# LoRa_XCVR.net
KiCad netlist of a schematic drawn in Altium Designer
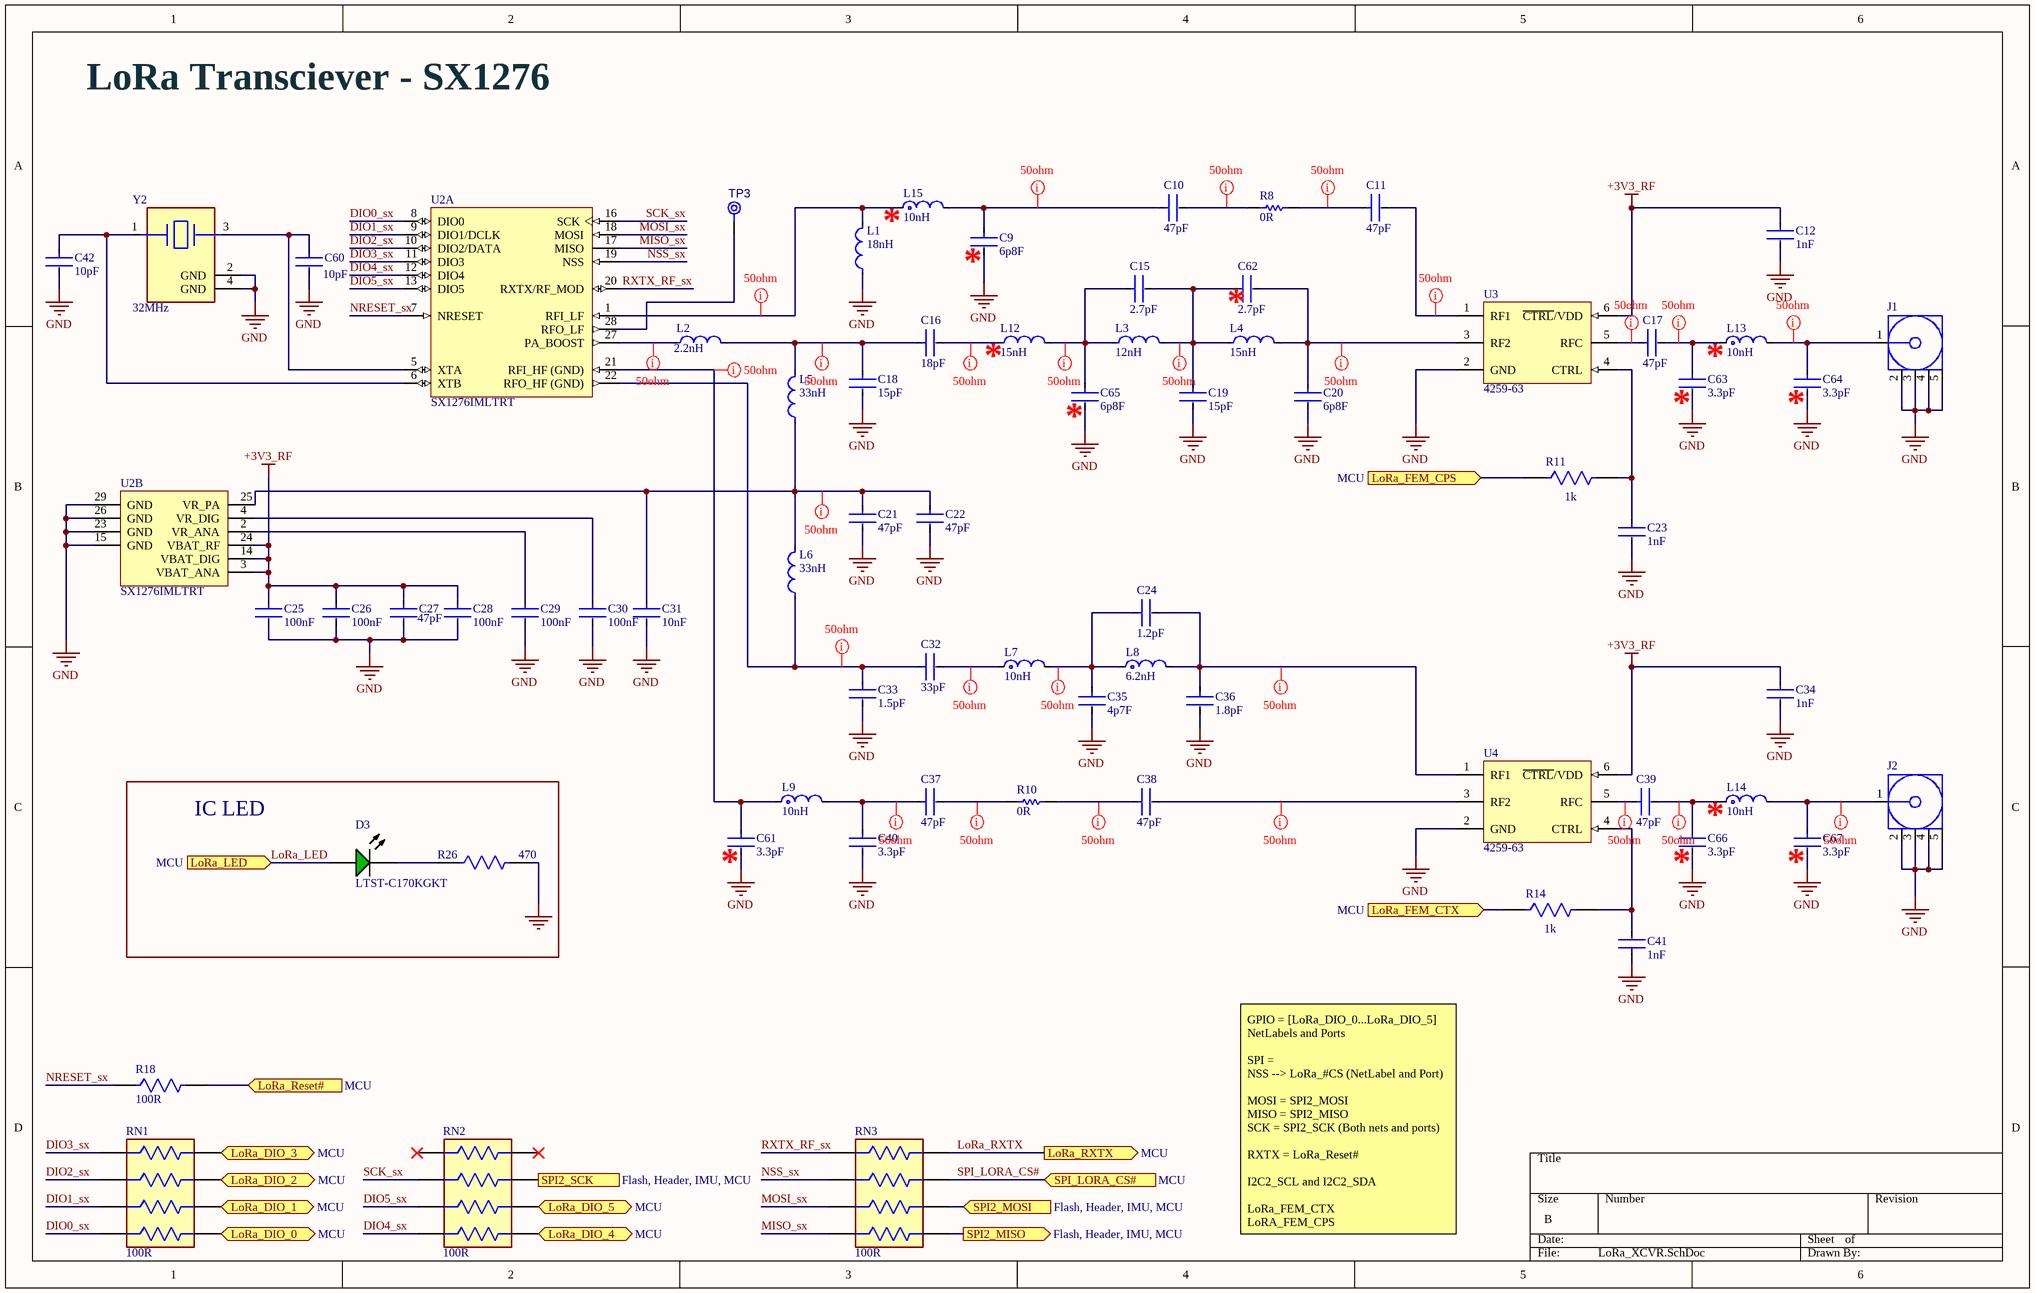
[diagram p0: LoRa_XCVR.SchDoc]

(export (version "E")
  (design (tool "Eeschema 10.0.6"))
  (components
    (comp (ref "C9")
      (value "6p8F")
      (footprint "FP-GJM155-0_05-IPC_A")
      (description "Multi-Layer Ceramic Capacitor 6.8pF C0G  ±0.1pF 0402 Paper T/R")
      (libsource (lib "Altium Content Vault") (part "02cd4be3c70576c341d710602a673aa"))
    )
    (comp (ref "C10")
      (value "47pF")
      (footprint "FP-GJM155-0_05-MFG")
      (description "Multi-Layer Ceramic Capacitor 47pF C0G  ±5% 0402 Paper T/R")
      (fields (field (name "TOLERANCE") "5%"))
      (libsource (lib "Altium Content Vault") (part "02cd4be3c70576c341d710602a673aa"))
    )
    (comp (ref "C11")
      (value "47pF")
      (footprint "FP-GJM155-0_05-MFG")
      (description "Multi-Layer Ceramic Capacitor 47pF C0G  ±5% 0402 Paper T/R")
      (fields (field (name "TOLERANCE") "5%"))
      (libsource (lib "Altium Content Vault") (part "02cd4be3c70576c341d710602a673aa"))
    )
    (comp (ref "C12")
      (value "1nF")
      (footprint "FP-GRM155-0_05-IPC_C")
      (description "Chip Multilayer Ceramic Capacitors for General Purpose, 0402, 1000pF, X7R, 15%, 10%, 100V")
      (fields (field (name "TOLERANCE") "10%") (field (name "VOLTAGE") "100V"))
      (libsource (lib "Altium Content Vault") (part "02cd4be3c70576c341d710602a673aa"))
    )
    (comp (ref "C15")
      (value "2.7pF")
      (footprint "FP-GJM155-0_05-IPC_A")
      (description "Multi-Layer Ceramic Capacitor 2.7pF C0G  ±0.1pF 0402 Paper T/R")
      (fields (field (name "VOLTAGE") "50V"))
      (libsource (lib "Altium Content Vault") (part "02cd4be3c70576c341d710602a673aa"))
    )
    (comp (ref "C16")
      (value "18pF")
      (footprint "FP-GJM155-0_05-IPC_B")
      (description "Multi-Layer Ceramic Capacitor 18pF C0G  ±5% 0402 Paper T/R")
      (fields (field (name "VOLTAGE") "50V") (field (name "TOLERANCE") "5%"))
      (libsource (lib "Altium Content Vault") (part "02cd4be3c70576c341d710602a673aa"))
    )
    (comp (ref "C17")
      (value "47pF")
      (footprint "FP-GJM155-0_05-MFG")
      (description "Multi-Layer Ceramic Capacitor 47pF C0G  ±5% 0402 Paper T/R")
      (fields (field (name "TOLERANCE") "5%"))
      (libsource (lib "Altium Content Vault") (part "02cd4be3c70576c341d710602a673aa"))
    )
    (comp (ref "C18")
      (value "15pF")
      (footprint "FP-GJM155-0_05-IPC_A")
      (description "Multi-Layer Ceramic Capacitor 15pF C0G  ±5% 0402 Paper T/R")
      (fields (field (name "TOLERANCE") "5%") (field (name "VOLTAGE") "50V"))
      (libsource (lib "Altium Content Vault") (part "02cd4be3c70576c341d710602a673aa"))
    )
    (comp (ref "C19")
      (value "15pF")
      (footprint "FP-GJM155-0_05-IPC_A")
      (description "Multi-Layer Ceramic Capacitor 15pF C0G  ±5% 0402 Paper T/R")
      (fields (field (name "TOLERANCE") "5%") (field (name "VOLTAGE") "50V"))
      (libsource (lib "Altium Content Vault") (part "02cd4be3c70576c341d710602a673aa"))
    )
    (comp (ref "C20")
      (value "6p8F")
      (footprint "FP-GJM155-0_05-IPC_A")
      (description "Multi-Layer Ceramic Capacitor 6.8pF C0G  ±0.1pF 0402 Paper T/R")
      (libsource (lib "Altium Content Vault") (part "02cd4be3c70576c341d710602a673aa"))
    )
    (comp (ref "C21")
      (value "47pF")
      (footprint "FP-GJM155-0_05-MFG")
      (description "Multi-Layer Ceramic Capacitor 47pF C0G  ±5% 0402 Paper T/R")
      (fields (field (name "TOLERANCE") "5%"))
      (libsource (lib "Altium Content Vault") (part "02cd4be3c70576c341d710602a673aa"))
    )
    (comp (ref "C22")
      (value "47pF")
      (footprint "FP-GJM155-0_05-MFG")
      (description "Multi-Layer Ceramic Capacitor 47pF C0G  ±5% 0402 Paper T/R")
      (fields (field (name "TOLERANCE") "5%"))
      (libsource (lib "Altium Content Vault") (part "02cd4be3c70576c341d710602a673aa"))
    )
    (comp (ref "C23")
      (value "1nF")
      (footprint "FP-GRM155-0_05-IPC_C")
      (description "Chip Multilayer Ceramic Capacitors for General Purpose, 0402, 1000pF, X7R, 15%, 10%, 100V")
      (fields (field (name "TOLERANCE") "10%") (field (name "VOLTAGE") "100V"))
      (libsource (lib "Altium Content Vault") (part "02cd4be3c70576c341d710602a673aa"))
    )
    (comp (ref "C24")
      (value "1.2pF")
      (footprint "FP-GJM155-0_05-IPC_B")
      (description "Multi-Layer Ceramic Capacitor 1.2pF C0G  ±0.1pF 0402 Paper T/R")
      (fields (field (name "VOLTAGE") "50V"))
      (libsource (lib "Altium Content Vault") (part "02cd4be3c70576c341d710602a673aa"))
    )
    (comp (ref "C25")
      (value "100nF")
      (footprint "FP-GRM155-0_05-IPC_B")
      (description "Chip Multilayer Ceramic Capacitors for General Purpose, 0402, 0.10uF, X7R, 15%, 10%, 50V")
      (fields (field (name "VOLTAGE") "50V") (field (name "TOLERANCE") "10%"))
      (libsource (lib "Altium Content Vault") (part "02cd4be3c70576c341d710602a673aa"))
    )
    (comp (ref "C26")
      (value "100nF")
      (footprint "FP-GRM155-0_05-IPC_B")
      (description "Chip Multilayer Ceramic Capacitors for General Purpose, 0402, 0.10uF, X7R, 15%, 10%, 50V")
      (fields (field (name "VOLTAGE") "50V") (field (name "TOLERANCE") "10%"))
      (libsource (lib "Altium Content Vault") (part "02cd4be3c70576c341d710602a673aa"))
    )
    (comp (ref "C27")
      (value "47pF")
      (footprint "FP-GJM155-0_05-MFG")
      (description "Multi-Layer Ceramic Capacitor 47pF C0G  ±5% 0402 Paper T/R")
      (fields (field (name "TOLERANCE") "5%"))
      (libsource (lib "Altium Content Vault") (part "02cd4be3c70576c341d710602a673aa"))
    )
    (comp (ref "C28")
      (value "100nF")
      (footprint "FP-GRM155-0_05-IPC_B")
      (description "Chip Multilayer Ceramic Capacitors for General Purpose, 0402, 0.10uF, X7R, 15%, 10%, 50V")
      (fields (field (name "VOLTAGE") "50V") (field (name "TOLERANCE") "10%"))
      (libsource (lib "Altium Content Vault") (part "02cd4be3c70576c341d710602a673aa"))
    )
    (comp (ref "C29")
      (value "100nF")
      (footprint "FP-GRM155-0_05-IPC_B")
      (description "Chip Multilayer Ceramic Capacitors for General Purpose, 0402, 0.10uF, X7R, 15%, 10%, 50V")
      (fields (field (name "VOLTAGE") "50V") (field (name "TOLERANCE") "10%"))
      (libsource (lib "Altium Content Vault") (part "02cd4be3c70576c341d710602a673aa"))
    )
    (comp (ref "C30")
      (value "100nF")
      (footprint "FP-GRM155-0_05-IPC_B")
      (description "Chip Multilayer Ceramic Capacitors for General Purpose, 0402, 0.10uF, X7R, 15%, 10%, 50V")
      (fields (field (name "VOLTAGE") "50V") (field (name "TOLERANCE") "10%"))
      (libsource (lib "Altium Content Vault") (part "02cd4be3c70576c341d710602a673aa"))
    )
    (comp (ref "C31")
      (value "10nF")
      (footprint "FP-GRM155-0_05-IPC_C")
      (description "Chip Multilayer Ceramic Capacitors for General Purpose, 0402, 10000pF, X7R, 15%, 10%, 50V")
      (fields (field (name "TOLERANCE") "10%") (field (name "VOLTAGE") "25V"))
      (libsource (lib "Altium Content Vault") (part "02cd4be3c70576c341d710602a673aa"))
    )
    (comp (ref "C32")
      (value "33pF")
      (footprint "FP-GJM155-0_05-MFG")
      (description "Multi-Layer Ceramic Capacitor 33pF C0G  ±5% 0402 Paper T/R")
      (fields (field (name "TOLERANCE") "5%"))
      (libsource (lib "Altium Content Vault") (part "02cd4be3c70576c341d710602a673aa"))
    )
    (comp (ref "C33")
      (value "1.5pF")
      (footprint "FP-GJM155-0_05-IPC_C")
      (description "Multi-Layer Ceramic Capacitor 1.5pF C0G  ±0.1pF 0402 Paper T/R")
      (fields (field (name "VOLTAGE") "50V"))
      (libsource (lib "Altium Content Vault") (part "02cd4be3c70576c341d710602a673aa"))
    )
    (comp (ref "C34")
      (value "1nF")
      (footprint "FP-GRM155-0_05-IPC_C")
      (description "Chip Multilayer Ceramic Capacitors for General Purpose, 0402, 1000pF, X7R, 15%, 10%, 100V")
      (fields (field (name "TOLERANCE") "10%") (field (name "VOLTAGE") "100V"))
      (libsource (lib "Altium Content Vault") (part "02cd4be3c70576c341d710602a673aa"))
    )
    (comp (ref "C35")
      (value "4p7F")
      (footprint "FP-GJM155-0_05-IPC_B")
      (description "Multi-Layer Ceramic Capacitor 4.7pF C0G  ±0.25pF 0402 Paper T/R")
      (fields (field (name "VOLTAGE") "50V"))
      (libsource (lib "Altium Content Vault") (part "02cd4be3c70576c341d710602a673aa"))
    )
    (comp (ref "C36")
      (value "1.8pF")
      (footprint "FP-GJM155-0_05-IPC_B")
      (description "Multi-Layer Ceramic Capacitor 1.8pF C0G  ±0.1pF 0402 Paper T/R")
      (fields (field (name "VOLTAGE") "50V"))
      (libsource (lib "Altium Content Vault") (part "02cd4be3c70576c341d710602a673aa"))
    )
    (comp (ref "C37")
      (value "47pF")
      (footprint "FP-GJM155-0_05-MFG")
      (description "Multi-Layer Ceramic Capacitor 47pF C0G  ±5% 0402 Paper T/R")
      (fields (field (name "TOLERANCE") "5%"))
      (libsource (lib "Altium Content Vault") (part "02cd4be3c70576c341d710602a673aa"))
    )
    (comp (ref "C38")
      (value "47pF")
      (footprint "FP-GJM155-0_05-MFG")
      (description "Multi-Layer Ceramic Capacitor 47pF C0G  ±5% 0402 Paper T/R")
      (fields (field (name "TOLERANCE") "5%"))
      (libsource (lib "Altium Content Vault") (part "02cd4be3c70576c341d710602a673aa"))
    )
    (comp (ref "C39")
      (value "47pF")
      (footprint "FP-GJM155-0_05-MFG")
      (description "Multi-Layer Ceramic Capacitor 47pF C0G  ±5% 0402 Paper T/R")
      (fields (field (name "TOLERANCE") "5%"))
      (libsource (lib "Altium Content Vault") (part "02cd4be3c70576c341d710602a673aa"))
    )
    (comp (ref "C40")
      (value "3.3pF")
      (footprint "FP-GJM155-0_05-IPC_C")
      (description "Multi-Layer Ceramic Capacitor 3.3pF C0G  ±0.1pF 0402 Paper T/R")
      (fields (field (name "VOLTAGE") "50V"))
      (libsource (lib "Altium Content Vault") (part "02cd4be3c70576c341d710602a673aa"))
    )
    (comp (ref "C41")
      (value "1nF")
      (footprint "FP-GRM155-0_05-IPC_C")
      (description "Chip Multilayer Ceramic Capacitors for General Purpose, 0402, 1000pF, X7R, 15%, 10%, 100V")
      (fields (field (name "TOLERANCE") "10%") (field (name "VOLTAGE") "100V"))
      (libsource (lib "Altium Content Vault") (part "02cd4be3c70576c341d710602a673aa"))
    )
    (comp (ref "C42")
      (value "10pF")
      (footprint "FP-GRT155-0_05-MFG")
      (description "Multi-Layer Ceramic Capacitor 10pF 50V C0G ±5% 0402 Paper T/R")
      (libsource (lib "Altium Content Vault") (part "02cd4be3c70576c341d710602a673aa"))
    )
    (comp (ref "C60")
      (value "10pF")
      (footprint "FP-GRT155-0_05-MFG")
      (description "Multi-Layer Ceramic Capacitor 10pF 50V C0G ±5% 0402 Paper T/R")
      (libsource (lib "Altium Content Vault") (part "02cd4be3c70576c341d710602a673aa"))
    )
    (comp (ref "C61")
      (value "3.3pF")
      (footprint "FP-GJM155-0_05-IPC_C")
      (description "Multi-Layer Ceramic Capacitor 3.3pF C0G  ±0.1pF 0402 Paper T/R")
      (fields (field (name "VOLTAGE") "50V"))
      (libsource (lib "Altium Content Vault") (part "02cd4be3c70576c341d710602a673aa"))
    )
    (comp (ref "C62")
      (value "2.7pF")
      (footprint "FP-GJM155-0_05-IPC_A")
      (description "Multi-Layer Ceramic Capacitor 2.7pF C0G  ±0.1pF 0402 Paper T/R")
      (fields (field (name "VOLTAGE") "50V"))
      (libsource (lib "Altium Content Vault") (part "02cd4be3c70576c341d710602a673aa"))
    )
    (comp (ref "C63")
      (value "3.3pF")
      (footprint "FP-GJM155-0_05-IPC_C")
      (description "Multi-Layer Ceramic Capacitor 3.3pF C0G  ±0.1pF 0402 Paper T/R")
      (fields (field (name "VOLTAGE") "50V"))
      (libsource (lib "Altium Content Vault") (part "02cd4be3c70576c341d710602a673aa"))
    )
    (comp (ref "C64")
      (value "3.3pF")
      (footprint "FP-GJM155-0_05-IPC_C")
      (description "Multi-Layer Ceramic Capacitor 3.3pF C0G  ±0.1pF 0402 Paper T/R")
      (fields (field (name "VOLTAGE") "50V"))
      (libsource (lib "Altium Content Vault") (part "02cd4be3c70576c341d710602a673aa"))
    )
    (comp (ref "C65")
      (value "6p8F")
      (footprint "FP-GJM155-0_05-IPC_A")
      (description "Multi-Layer Ceramic Capacitor 6.8pF C0G  ±0.1pF 0402 Paper T/R")
      (libsource (lib "Altium Content Vault") (part "02cd4be3c70576c341d710602a673aa"))
    )
    (comp (ref "C66")
      (value "3.3pF")
      (footprint "FP-GJM155-0_05-IPC_C")
      (description "Multi-Layer Ceramic Capacitor 3.3pF C0G  ±0.1pF 0402 Paper T/R")
      (fields (field (name "VOLTAGE") "50V"))
      (libsource (lib "Altium Content Vault") (part "02cd4be3c70576c341d710602a673aa"))
    )
    (comp (ref "C67")
      (value "3.3pF")
      (footprint "FP-GJM155-0_05-IPC_C")
      (description "Multi-Layer Ceramic Capacitor 3.3pF C0G  ±0.1pF 0402 Paper T/R")
      (fields (field (name "VOLTAGE") "50V"))
      (libsource (lib "Altium Content Vault") (part "02cd4be3c70576c341d710602a673aa"))
    )
    (comp (ref "D3")
      (value "LTST-C170KGKT")
      (footprint "LTST-LTST-C170KGKT-2_V")
      (description "Ultra Bright AlInGaP Chip LED, 75 mW, -55 to 85 degC, 2-Pin SMD (0805), RoHS, Tape and Reel")
      (fields (field (name "MANUFACTURER") "Lite-On"))
      (libsource (lib "Altium Content Vault") (part "LED-GREEN-KA-2"))
    )
    (comp (ref "J1")
      (value "142-0701-801")
      (footprint "CINC-142-0701-801_V")
      (description "SMA End Launch Jack Receptacle, 50 Ohm, 0 to 18 GHz, -65 to 165 degC, 5-Pin SMD, RoHS, Bulk")
      (fields (field (name "MANUFACTURER") "EmersonConnectivitySolutions"))
      (libsource (lib "Altium Content Vault") (part "CN-S-4F-RF5"))
    )
    (comp (ref "J2")
      (value "142-0701-801")
      (footprint "CINC-142-0701-801_V")
      (description "SMA End Launch Jack Receptacle, 50 Ohm, 0 to 18 GHz, -65 to 165 degC, 5-Pin SMD, RoHS, Bulk")
      (fields (field (name "MANUFACTURER") "EmersonConnectivitySolutions"))
      (libsource (lib "Altium Content Vault") (part "CN-S-4F-RF5"))
    )
    (comp (ref "L1")
      (value "18nH")
      (footprint "FP-LQW15AN_00-W0_6-0_1-MFG")
      (description "Wire Wound RF Inductor 18nH ±5% 370mA 0.27Ω 0402 (1005)")
      (fields (field (name "TOLERANCE") "5%"))
      (libsource (lib "Altium Content Vault") (part "725321dda6339637d4d059423bc1c3c"))
    )
    (comp (ref "L2")
      (value "2.2nH")
      (footprint "FP-LQW15AN_00-W0_6-0_1-MFG")
      (description "Wire Wound RF Inductor 2.2nH ±0.2nH 1000mA 0.027Ω 0402 (1005)")
      (libsource (lib "Altium Content Vault") (part "725321dda6339637d4d059423bc1c3c"))
    )
    (comp (ref "L3")
      (value "12nH")
      (footprint "FP-LQW15AN_00-W0_6-0_1-MFG")
      (description "Wire Wound RF Inductor 12nH ±5% 500mA 0.14Ω 0402 (1005)")
      (fields (field (name "TOLERANCE") "5%"))
      (libsource (lib "Altium Content Vault") (part "725321dda6339637d4d059423bc1c3c"))
    )
    (comp (ref "L4")
      (value "15nH")
      (footprint "FP-LQW15AN_00-W0_6-0_1-MFG")
      (description "Wire Wound RF Inductor 15nH ±5% 460mA 0.16Ω 0402 (1005)")
      (fields (field (name "TOLERANCE") "5%"))
      (libsource (lib "Altium Content Vault") (part "725321dda6339637d4d059423bc1c3c"))
    )
    (comp (ref "L5")
      (value "33nH")
      (footprint "FP-LQW15AN_00-W0_5-0_1-MFG")
      (description "Wire Wound RF Inductor 33nH ±5% 260mA 0.63Ω 0402 (1005)")
      (fields (field (name "TOLERANCE") "5%"))
      (libsource (lib "Altium Content Vault") (part "725321dda6339637d4d059423bc1c3c"))
    )
    (comp (ref "L6")
      (value "33nH")
      (footprint "FP-LQW15AN_00-W0_5-0_1-MFG")
      (description "Wire Wound RF Inductor 33nH ±5% 260mA 0.63Ω 0402 (1005)")
      (fields (field (name "TOLERANCE") "5%"))
      (libsource (lib "Altium Content Vault") (part "725321dda6339637d4d059423bc1c3c"))
    )
    (comp (ref "L7")
      (value "10nH")
      (footprint "FP-LQG15HH_02-IPC_A")
      (description "Multilayer type RF Inductor 10nH ±5% 0.26Ω 500mA 0402")
      (fields (field (name "TOLERANCE") "5%"))
      (libsource (lib "Altium Content Vault") (part "4cc4b267dca4c8e51f7102f422741d8"))
    )
    (comp (ref "L8")
      (value "6.2nH")
      (footprint "FP-LQG15HH_02-IPC_C")
      (description "Multilayer type RF Inductor 6.2nH ±0.3nH 0.2Ω 600mA 0402")
      (libsource (lib "Altium Content Vault") (part "4cc4b267dca4c8e51f7102f422741d8"))
    )
    (comp (ref "L9")
      (value "10nH")
      (footprint "FP-LQG15HH_02-IPC_A")
      (description "Multilayer type RF Inductor 10nH ±5% 0.26Ω 500mA 0402")
      (fields (field (name "TOLERANCE") "5%"))
      (libsource (lib "Altium Content Vault") (part "4cc4b267dca4c8e51f7102f422741d8"))
    )
    (comp (ref "L12")
      (value "15nH")
      (footprint "FP-LQW15AN_00-W0_6-0_1-MFG")
      (description "Wire Wound RF Inductor 15nH ±5% 460mA 0.16Ω 0402 (1005)")
      (fields (field (name "TOLERANCE") "5%"))
      (libsource (lib "Altium Content Vault") (part "725321dda6339637d4d059423bc1c3c"))
    )
    (comp (ref "L13")
      (value "10nH")
      (footprint "FP-LQG15HH_02-IPC_A")
      (description "Multilayer type RF Inductor 10nH ±5% 0.26Ω 500mA 0402")
      (fields (field (name "TOLERANCE") "5%"))
      (libsource (lib "Altium Content Vault") (part "4cc4b267dca4c8e51f7102f422741d8"))
    )
    (comp (ref "L14")
      (value "10nH")
      (footprint "FP-LQG15HH_02-IPC_A")
      (description "Multilayer type RF Inductor 10nH ±5% 0.26Ω 500mA 0402")
      (fields (field (name "TOLERANCE") "5%"))
      (libsource (lib "Altium Content Vault") (part "4cc4b267dca4c8e51f7102f422741d8"))
    )
    (comp (ref "L15")
      (value "10nH")
      (footprint "FP-LQG15HH_02-IPC_A")
      (description "Multilayer type RF Inductor 10nH ±5% 0.26Ω 500mA 0402")
      (fields (field (name "TOLERANCE") "5%"))
      (libsource (lib "Altium Content Vault") (part "4cc4b267dca4c8e51f7102f422741d8"))
    )
    (comp (ref "R8")
      (value "0R")
      (footprint "RESC1005X40X25LL05T05")
      (description "Chip Resistor, 0 Ohm, 0.1 W, -55 to 155 degC, 0402 (1005 Metric), RoHS, Tape and Reel")
      (fields (field (name "MANUFACTURER") "Panasonic") (field (name "TOLERANCE") "5%"))
      (libsource (lib "Altium Content Vault") (part "RES-2"))
    )
    (comp (ref "R10")
      (value "0R")
      (footprint "RESC1005X40X25LL05T05")
      (description "Chip Resistor, 0 Ohm, 0.1 W, -55 to 155 degC, 0402 (1005 Metric), RoHS, Tape and Reel")
      (fields (field (name "MANUFACTURER") "Panasonic") (field (name "TOLERANCE") "5%"))
      (libsource (lib "Altium Content Vault") (part "RES-2"))
    )
    (comp (ref "R11")
      (value "1k")
      (footprint "FP-CRCW0402-e3-MFG")
      (description "RES Thick Film, 1kΩ, 5%, 0.063W, 200ppm/°C, 0402")
      (fields (field (name "TOLERANCE") "5%"))
      (libsource (lib "Altium Content Vault") (part "1029c3af85768c4190bb7ad29bc67b5"))
    )
    (comp (ref "R14")
      (value "1k")
      (footprint "FP-CRCW0402-e3-MFG")
      (description "RES Thick Film, 1kΩ, 5%, 0.063W, 200ppm/°C, 0402")
      (fields (field (name "TOLERANCE") "5%"))
      (libsource (lib "Altium Content Vault") (part "1029c3af85768c4190bb7ad29bc67b5"))
    )
    (comp (ref "R18")
      (value "100R")
      (footprint "FP-CRCW0402-e3-IPC_A")
      (description "RES Thick Film, 100Ω, 5%, 0.063W, 200ppm/°C, 0402")
      (fields (field (name "TOLERANCE") "5%"))
      (libsource (lib "Altium Content Vault") (part "1029c3af85768c4190bb7ad29bc67b5"))
    )
    (comp (ref "R26")
      (value "470")
      (footprint "FP-CPF0603-MFG")
      (description "RES SMD 470Ω 0.1% 1/16W 0603\r\n\r\nCPF0603B470RE")
      (fields
        (field (name "MANUFACTURER") "TE Connectivity")
        (field (name "MANUFACTURER PART NUMBER") "CPF0603B470RE")
      )
      (libsource (lib "Altium Content Vault") (part "1029c3af85768c4190bb7ad29bc67b5"))
    )
    (comp (ref "RN1")
      (value "100R")
      (footprint "FP-EXB38V-MFG")
      (description "RES ARRAY 4 RES 100 OHM 1206")
      (fields (field (name "TOLERANCE") "5%"))
      (libsource (lib "Altium Content Vault") (part "4cbe94bce750996fb93abba432e828f"))
    )
    (comp (ref "RN2")
      (value "100R")
      (footprint "FP-EXB38V-MFG")
      (description "RES ARRAY 4 RES 100 OHM 1206")
      (fields (field (name "TOLERANCE") "5%"))
      (libsource (lib "Altium Content Vault") (part "4cbe94bce750996fb93abba432e828f"))
    )
    (comp (ref "RN3")
      (value "100R")
      (footprint "FP-EXB38V-MFG")
      (description "RES ARRAY 4 RES 100 OHM 1206")
      (fields (field (name "TOLERANCE") "5%"))
      (libsource (lib "Altium Content Vault") (part "4cbe94bce750996fb93abba432e828f"))
    )
    (comp (ref "TP3")
      (value "TPAD6R")
      (footprint "TP06R")
      (description "0.6mm round")
      (libsource (lib "Personal Repository") (part "CMP-001-0001-4"))
    )
    (comp (ref "U2")
      (value "SX1276IMLTRT")
      (footprint "SMTC-QFN-28_V")
      (description "Low Power Long Range Transceiver, 137 to 1020 MHz, -40 to 85 degC, 28-Pin QFN, RoHS, Tape and Reel")
      (fields (field (name "MANUFACTURER") "Semtech"))
      (libsource (lib "Altium Content Vault") (part "SMTC-SX127X-QFN-28"))
    )
    (comp (ref "U3")
      (value "4259-63")
      (footprint "PERE-SC-70-6_M")
      (description "IC RF Switch SPDT, 50 Ohm, 6-Pin SC70, RoHS, Tape and Reel")
      (fields (field (name "MANUFACTURER") "Peregrine Semiconductor"))
      (libsource (lib "Altium Content Vault") (part "PERE-PE4259-6"))
    )
    (comp (ref "U4")
      (value "4259-63")
      (footprint "PERE-SC-70-6_M")
      (description "IC RF Switch SPDT, 50 Ohm, 6-Pin SC70, RoHS, Tape and Reel")
      (fields (field (name "MANUFACTURER") "Peregrine Semiconductor"))
      (libsource (lib "Altium Content Vault") (part "PERE-PE4259-6"))
    )
    (comp (ref "Y2")
      (value "32MHz")
      (footprint "FP-ABM11-MFG")
      (description "Crystal 32MHz ±10ppm 10pF SMD-4 2mm x 1.6mm")
      (libsource (lib "Altium Content Vault") (part "b3c1237d77310e73098bcf11eecb25f"))
    )
  )
  (nets
    (net (code "1") (name "+3V3_RF") (class "Default")
      (node (ref "C12") (pin "1") (pinfunction "1_1") (pintype "passive"))
      (node (ref "C25") (pin "1") (pinfunction "1_1") (pintype "passive"))
      (node (ref "C26") (pin "1") (pinfunction "1_1") (pintype "passive"))
      (node (ref "C27") (pin "1") (pinfunction "1_1") (pintype "passive"))
      (node (ref "C28") (pin "1") (pinfunction "1_1") (pintype "passive"))
      (node (ref "C34") (pin "1") (pinfunction "1_1") (pintype "passive"))
      (node (ref "U2") (pin "14") (pinfunction "VBAT_DIG_14") (pintype "power_in"))
      (node (ref "U2") (pin "24") (pinfunction "VBAT_RF_24") (pintype "power_in"))
      (node (ref "U2") (pin "3") (pinfunction "VBAT_ANA_3") (pintype "power_in"))
      (node (ref "U3") (pin "6") (pinfunction "~{CTRL}/VDD_6") (pintype "input"))
      (node (ref "U4") (pin "6") (pinfunction "~{CTRL}/VDD_6") (pintype "input"))
    )
    (net (code "2") (name "/DIO0_sx") (class "Default")
      (node (ref "RN1") (pin "4") (pinfunction "4_4") (pintype "passive"))
      (node (ref "U2") (pin "8") (pinfunction "DIO0_8") (pintype "bidirectional"))
    )
    (net (code "3") (name "/DIO1_sx") (class "Default")
      (node (ref "RN1") (pin "3") (pinfunction "3_3") (pintype "passive"))
      (node (ref "U2") (pin "9") (pinfunction "DIO1/DCLK_9") (pintype "bidirectional"))
    )
    (net (code "4") (name "/DIO2_sx") (class "Default")
      (node (ref "RN1") (pin "2") (pinfunction "2_2") (pintype "passive"))
      (node (ref "U2") (pin "10") (pinfunction "DIO2/DATA_10") (pintype "bidirectional"))
    )
    (net (code "5") (name "/DIO3_sx") (class "Default")
      (node (ref "RN1") (pin "1") (pinfunction "1_1") (pintype "passive"))
      (node (ref "U2") (pin "11") (pinfunction "DIO3_11") (pintype "bidirectional"))
    )
    (net (code "6") (name "/DIO4_sx") (class "Default")
      (node (ref "RN2") (pin "4") (pinfunction "4_4") (pintype "passive"))
      (node (ref "U2") (pin "12") (pinfunction "DIO4_12") (pintype "bidirectional"))
    )
    (net (code "7") (name "/DIO5_sx") (class "Default")
      (node (ref "RN2") (pin "3") (pinfunction "3_3") (pintype "passive"))
      (node (ref "U2") (pin "13") (pinfunction "DIO5_13") (pintype "bidirectional"))
    )
    (net (code "8") (name "/LoRa_DIO_0") (class "Default")
      (node (ref "RN1") (pin "5") (pinfunction "5_5") (pintype "passive"))
    )
    (net (code "9") (name "/LoRa_DIO_1") (class "Default")
      (node (ref "RN1") (pin "6") (pinfunction "6_6") (pintype "passive"))
    )
    (net (code "10") (name "/LoRa_DIO_2") (class "Default")
      (node (ref "RN1") (pin "7") (pinfunction "7_7") (pintype "passive"))
    )
    (net (code "11") (name "/LoRa_DIO_3") (class "Default")
      (node (ref "RN1") (pin "8") (pinfunction "8_8") (pintype "passive"))
    )
    (net (code "12") (name "/LoRa_DIO_4") (class "Default")
      (node (ref "RN2") (pin "5") (pinfunction "5_5") (pintype "passive"))
    )
    (net (code "13") (name "/LoRa_DIO_5") (class "Default")
      (node (ref "RN2") (pin "6") (pinfunction "6_6") (pintype "passive"))
    )
    (net (code "14") (name "/LoRa_FEM_CPS") (class "Default")
      (node (ref "R11") (pin "1") (pinfunction "1_1") (pintype "passive"))
    )
    (net (code "15") (name "/LoRa_FEM_CTX") (class "Default")
      (node (ref "R14") (pin "1") (pinfunction "1_1") (pintype "passive"))
    )
    (net (code "16") (name "/LoRa_LED") (class "Default")
      (node (ref "D3") (pin "2") (pinfunction "A_2") (pintype "passive"))
    )
    (net (code "17") (name "/LoRa_RXTX") (class "Default")
      (node (ref "RN3") (pin "8") (pinfunction "8_8") (pintype "passive"))
    )
    (net (code "18") (name "/LoRa_Reset#") (class "Default")
      (node (ref "R18") (pin "2") (pinfunction "2_2") (pintype "passive"))
    )
    (net (code "19") (name "/MISO_sx") (class "Default")
      (node (ref "RN3") (pin "4") (pinfunction "4_4") (pintype "passive"))
      (node (ref "U2") (pin "17") (pinfunction "MISO_17") (pintype "tri_state"))
    )
    (net (code "20") (name "/MOSI_sx") (class "Default")
      (node (ref "RN3") (pin "3") (pinfunction "3_3") (pintype "passive"))
      (node (ref "U2") (pin "18") (pinfunction "MOSI_18") (pintype "input"))
    )
    (net (code "21") (name "/NRESET_sx") (class "Default")
      (node (ref "R18") (pin "1") (pinfunction "1_1") (pintype "passive"))
      (node (ref "U2") (pin "7") (pinfunction "NRESET_7") (pintype "input"))
    )
    (net (code "22") (name "/NSS_sx") (class "Default")
      (node (ref "RN3") (pin "2") (pinfunction "2_2") (pintype "passive"))
      (node (ref "U2") (pin "19") (pinfunction "NSS_19") (pintype "input"))
    )
    (net (code "23") (name "/RXTX_RF_sx") (class "Default")
      (node (ref "RN3") (pin "1") (pinfunction "1_1") (pintype "passive"))
      (node (ref "U2") (pin "20") (pinfunction "RXTX/RF_MOD_20") (pintype "bidirectional"))
    )
    (net (code "24") (name "/SCK_sx") (class "Default")
      (node (ref "RN2") (pin "2") (pinfunction "2_2") (pintype "passive"))
      (node (ref "U2") (pin "16") (pinfunction "SCK_16") (pintype "input"))
    )
    (net (code "25") (name "/SPI2_MISO") (class "Default")
      (node (ref "RN3") (pin "5") (pinfunction "5_5") (pintype "passive"))
    )
    (net (code "26") (name "/SPI2_MOSI") (class "Default")
      (node (ref "RN3") (pin "6") (pinfunction "6_6") (pintype "passive"))
    )
    (net (code "27") (name "/SPI2_SCK") (class "Default")
      (node (ref "RN2") (pin "7") (pinfunction "7_7") (pintype "passive"))
    )
    (net (code "28") (name "/SPI_LORA_CS#") (class "Default")
      (node (ref "RN3") (pin "7") (pinfunction "7_7") (pintype "passive"))
    )
    (net (code "29") (name "GND") (class "Default")
      (node (ref "C12") (pin "2") (pinfunction "2_2") (pintype "passive"))
      (node (ref "C18") (pin "2") (pinfunction "2_2") (pintype "passive"))
      (node (ref "C19") (pin "2") (pinfunction "2_2") (pintype "passive"))
      (node (ref "C20") (pin "2") (pinfunction "2_2") (pintype "passive"))
      (node (ref "C21") (pin "2") (pinfunction "2_2") (pintype "passive"))
      (node (ref "C22") (pin "2") (pinfunction "2_2") (pintype "passive"))
      (node (ref "C23") (pin "2") (pinfunction "2_2") (pintype "passive"))
      (node (ref "C25") (pin "2") (pinfunction "2_2") (pintype "passive"))
      (node (ref "C26") (pin "2") (pinfunction "2_2") (pintype "passive"))
      (node (ref "C27") (pin "2") (pinfunction "2_2") (pintype "passive"))
      (node (ref "C28") (pin "2") (pinfunction "2_2") (pintype "passive"))
      (node (ref "C29") (pin "2") (pinfunction "2_2") (pintype "passive"))
      (node (ref "C30") (pin "2") (pinfunction "2_2") (pintype "passive"))
      (node (ref "C31") (pin "2") (pinfunction "2_2") (pintype "passive"))
      (node (ref "C33") (pin "2") (pinfunction "2_2") (pintype "passive"))
      (node (ref "C34") (pin "2") (pinfunction "2_2") (pintype "passive"))
      (node (ref "C35") (pin "2") (pinfunction "2_2") (pintype "passive"))
      (node (ref "C36") (pin "2") (pinfunction "2_2") (pintype "passive"))
      (node (ref "C40") (pin "2") (pinfunction "2_2") (pintype "passive"))
      (node (ref "C41") (pin "1") (pinfunction "1_1") (pintype "passive"))
      (node (ref "C42") (pin "2") (pinfunction "2_2") (pintype "passive"))
      (node (ref "C60") (pin "2") (pinfunction "2_2") (pintype "passive"))
      (node (ref "C61") (pin "2") (pinfunction "2_2") (pintype "passive"))
      (node (ref "C63") (pin "2") (pinfunction "2_2") (pintype "passive"))
      (node (ref "C64") (pin "2") (pinfunction "2_2") (pintype "passive"))
      (node (ref "C65") (pin "2") (pinfunction "2_2") (pintype "passive"))
      (node (ref "C66") (pin "2") (pinfunction "2_2") (pintype "passive"))
      (node (ref "C67") (pin "2") (pinfunction "2_2") (pintype "passive"))
      (node (ref "C9") (pin "2") (pinfunction "2_2") (pintype "passive"))
      (node (ref "J1") (pin "2") (pinfunction "2_2") (pintype "passive"))
      (node (ref "J1") (pin "3") (pinfunction "3_3") (pintype "passive"))
      (node (ref "J1") (pin "4") (pinfunction "4_4") (pintype "passive"))
      (node (ref "J1") (pin "5") (pinfunction "5_5") (pintype "passive"))
      (node (ref "J2") (pin "2") (pinfunction "2_2") (pintype "passive"))
      (node (ref "J2") (pin "3") (pinfunction "3_3") (pintype "passive"))
      (node (ref "J2") (pin "4") (pinfunction "4_4") (pintype "passive"))
      (node (ref "J2") (pin "5") (pinfunction "5_5") (pintype "passive"))
      (node (ref "L1") (pin "1") (pinfunction "1_1") (pintype "passive"))
      (node (ref "R26") (pin "2") (pinfunction "2_2") (pintype "passive"))
      (node (ref "U2") (pin "15") (pinfunction "GND_15") (pintype "power_in"))
      (node (ref "U2") (pin "23") (pinfunction "GND_23") (pintype "power_in"))
      (node (ref "U2") (pin "26") (pinfunction "GND_26") (pintype "power_in"))
      (node (ref "U2") (pin "29") (pinfunction "GND_29") (pintype "power_in"))
      (node (ref "U3") (pin "2") (pinfunction "GND_2") (pintype "power_in"))
      (node (ref "U4") (pin "2") (pinfunction "GND_2") (pintype "power_in"))
      (node (ref "Y2") (pin "2") (pinfunction "GND_2") (pintype "power_in"))
      (node (ref "Y2") (pin "4") (pinfunction "GND_4") (pintype "power_in"))
    )
    (net (code "30") (name "Net-(C10-Pad1)") (class "Default")
      (node (ref "C10") (pin "1") (pinfunction "1_1") (pintype "passive"))
      (node (ref "C9") (pin "1") (pinfunction "1_1") (pintype "passive"))
      (node (ref "L15") (pin "2") (pinfunction "2_2") (pintype "passive"))
    )
    (net (code "31") (name "Net-(C10-Pad2)") (class "Default")
      (node (ref "C10") (pin "2") (pinfunction "2_2") (pintype "passive"))
      (node (ref "R8") (pin "1") (pinfunction "1_1") (pintype "passive"))
    )
    (net (code "32") (name "Net-(C11-Pad1)") (class "Default")
      (node (ref "C11") (pin "1") (pinfunction "1_1") (pintype "passive"))
      (node (ref "R8") (pin "2") (pinfunction "2_2") (pintype "passive"))
    )
    (net (code "33") (name "Net-(C15-Pad1)") (class "Default")
      (node (ref "C15") (pin "1") (pinfunction "1_1") (pintype "passive"))
      (node (ref "C65") (pin "1") (pinfunction "1_1") (pintype "passive"))
      (node (ref "L12") (pin "2") (pinfunction "2_2") (pintype "passive"))
      (node (ref "L3") (pin "1") (pinfunction "1_1") (pintype "passive"))
    )
    (net (code "34") (name "Net-(C15-Pad2)") (class "Default")
      (node (ref "C15") (pin "2") (pinfunction "2_2") (pintype "passive"))
      (node (ref "C19") (pin "1") (pinfunction "1_1") (pintype "passive"))
      (node (ref "C62") (pin "1") (pinfunction "1_1") (pintype "passive"))
      (node (ref "L3") (pin "2") (pinfunction "2_2") (pintype "passive"))
      (node (ref "L4") (pin "1") (pinfunction "1_1") (pintype "passive"))
    )
    (net (code "35") (name "Net-(C16-Pad1)") (class "Default")
      (node (ref "C16") (pin "1") (pinfunction "1_1") (pintype "passive"))
      (node (ref "C18") (pin "1") (pinfunction "1_1") (pintype "passive"))
      (node (ref "L2") (pin "2") (pinfunction "2_2") (pintype "passive"))
      (node (ref "L5") (pin "2") (pinfunction "2_2") (pintype "passive"))
    )
    (net (code "36") (name "Net-(C16-Pad2)") (class "Default")
      (node (ref "C16") (pin "2") (pinfunction "2_2") (pintype "passive"))
      (node (ref "L12") (pin "1") (pinfunction "1_1") (pintype "passive"))
    )
    (net (code "37") (name "Net-(C17-Pad2)") (class "Default")
      (node (ref "C17") (pin "2") (pinfunction "2_2") (pintype "passive"))
      (node (ref "C63") (pin "1") (pinfunction "1_1") (pintype "passive"))
      (node (ref "L13") (pin "1") (pinfunction "1_1") (pintype "passive"))
    )
    (net (code "38") (name "Net-(C24-Pad1)") (class "Default")
      (node (ref "C24") (pin "1") (pinfunction "1_1") (pintype "passive"))
      (node (ref "C35") (pin "1") (pinfunction "1_1") (pintype "passive"))
      (node (ref "L7") (pin "2") (pinfunction "2_2") (pintype "passive"))
      (node (ref "L8") (pin "1") (pinfunction "1_1") (pintype "passive"))
    )
    (net (code "39") (name "Net-(C32-Pad2)") (class "Default")
      (node (ref "C32") (pin "2") (pinfunction "2_2") (pintype "passive"))
      (node (ref "L7") (pin "1") (pinfunction "1_1") (pintype "passive"))
    )
    (net (code "40") (name "Net-(C37-Pad1)") (class "Default")
      (node (ref "C37") (pin "1") (pinfunction "1_1") (pintype "passive"))
      (node (ref "C40") (pin "1") (pinfunction "1_1") (pintype "passive"))
      (node (ref "L9") (pin "2") (pinfunction "2_2") (pintype "passive"))
    )
    (net (code "41") (name "Net-(C37-Pad2)") (class "Default")
      (node (ref "C37") (pin "2") (pinfunction "2_2") (pintype "passive"))
      (node (ref "R10") (pin "1") (pinfunction "1_1") (pintype "passive"))
    )
    (net (code "42") (name "Net-(C38-Pad1)") (class "Default")
      (node (ref "C38") (pin "1") (pinfunction "1_1") (pintype "passive"))
      (node (ref "R10") (pin "2") (pinfunction "2_2") (pintype "passive"))
    )
    (net (code "43") (name "Net-(C39-Pad2)") (class "Default")
      (node (ref "C39") (pin "2") (pinfunction "2_2") (pintype "passive"))
      (node (ref "C66") (pin "1") (pinfunction "1_1") (pintype "passive"))
      (node (ref "L14") (pin "1") (pinfunction "1_1") (pintype "passive"))
    )
    (net (code "44") (name "Net-(C64-Pad1)") (class "Default")
      (node (ref "C64") (pin "1") (pinfunction "1_1") (pintype "passive"))
      (node (ref "J1") (pin "1") (pinfunction "1_1") (pintype "passive"))
      (node (ref "L13") (pin "2") (pinfunction "2_2") (pintype "passive"))
    )
    (net (code "45") (name "Net-(C67-Pad1)") (class "Default")
      (node (ref "C67") (pin "1") (pinfunction "1_1") (pintype "passive"))
      (node (ref "J2") (pin "1") (pinfunction "1_1") (pintype "passive"))
      (node (ref "L14") (pin "2") (pinfunction "2_2") (pintype "passive"))
    )
    (net (code "46") (name "Net-(D3-K)") (class "Default")
      (node (ref "D3") (pin "1") (pinfunction "K_1") (pintype "passive"))
      (node (ref "R26") (pin "1") (pinfunction "1_1") (pintype "passive"))
    )
    (net (code "47") (name "Net-(TP3-TP)") (class "Default")
      (node (ref "TP3") (pin "1") (pinfunction "TP_1") (pintype "passive"))
      (node (ref "U2") (pin "28") (pinfunction "RFO_LF_28") (pintype "output"))
    )
    (net (code "48") (name "Net-(U2A-PA_BOOST)") (class "Default")
      (node (ref "L2") (pin "1") (pinfunction "1_1") (pintype "passive"))
      (node (ref "U2") (pin "27") (pinfunction "PA_BOOST_27") (pintype "output"))
    )
    (net (code "49") (name "Net-(U2A-RFI_HF_(GND))") (class "Default")
      (node (ref "C61") (pin "1") (pinfunction "1_1") (pintype "passive"))
      (node (ref "L9") (pin "1") (pinfunction "1_1") (pintype "passive"))
      (node (ref "U2") (pin "21") (pinfunction "RFI_HF_(GND)_21") (pintype "input"))
    )
    (net (code "50") (name "Net-(U2A-RFI_LF)") (class "Default")
      (node (ref "L1") (pin "2") (pinfunction "2_2") (pintype "passive"))
      (node (ref "L15") (pin "1") (pinfunction "1_1") (pintype "passive"))
      (node (ref "U2") (pin "1") (pinfunction "RFI_LF_1") (pintype "input"))
    )
    (net (code "51") (name "Net-(U2A-RFO_HF_(GND))") (class "Default")
      (node (ref "C32") (pin "1") (pinfunction "1_1") (pintype "passive"))
      (node (ref "C33") (pin "1") (pinfunction "1_1") (pintype "passive"))
      (node (ref "L6") (pin "1") (pinfunction "1_1") (pintype "passive"))
      (node (ref "U2") (pin "22") (pinfunction "RFO_HF_(GND)_22") (pintype "output"))
    )
    (net (code "52") (name "Net-(U2A-XTA)") (class "Default")
      (node (ref "C60") (pin "1") (pinfunction "1_1") (pintype "passive"))
      (node (ref "U2") (pin "5") (pinfunction "XTA_5") (pintype "bidirectional"))
      (node (ref "Y2") (pin "3") (pinfunction "3_3") (pintype "passive"))
    )
    (net (code "53") (name "Net-(U2A-XTB)") (class "Default")
      (node (ref "C42") (pin "1") (pinfunction "1_1") (pintype "passive"))
      (node (ref "U2") (pin "6") (pinfunction "XTB_6") (pintype "bidirectional"))
      (node (ref "Y2") (pin "1") (pinfunction "1_1") (pintype "passive"))
    )
    (net (code "54") (name "Net-(U2B-VR_ANA)") (class "Default")
      (node (ref "C29") (pin "1") (pinfunction "1_1") (pintype "passive"))
      (node (ref "U2") (pin "2") (pinfunction "VR_ANA_2") (pintype "power_in"))
    )
    (net (code "55") (name "Net-(U2B-VR_DIG)") (class "Default")
      (node (ref "C30") (pin "1") (pinfunction "1_1") (pintype "passive"))
      (node (ref "U2") (pin "4") (pinfunction "VR_DIG_4") (pintype "power_in"))
    )
    (net (code "56") (name "Net-(U2B-VR_PA)") (class "Default")
      (node (ref "C21") (pin "1") (pinfunction "1_1") (pintype "passive"))
      (node (ref "C22") (pin "1") (pinfunction "1_1") (pintype "passive"))
      (node (ref "C31") (pin "1") (pinfunction "1_1") (pintype "passive"))
      (node (ref "L5") (pin "1") (pinfunction "1_1") (pintype "passive"))
      (node (ref "L6") (pin "2") (pinfunction "2_2") (pintype "passive"))
      (node (ref "U2") (pin "25") (pinfunction "VR_PA_25") (pintype "power_in"))
    )
    (net (code "57") (name "Net-(U3-CTRL)") (class "Default")
      (node (ref "C23") (pin "1") (pinfunction "1_1") (pintype "passive"))
      (node (ref "R11") (pin "2") (pinfunction "2_2") (pintype "passive"))
      (node (ref "U3") (pin "4") (pinfunction "CTRL_4") (pintype "input"))
    )
    (net (code "58") (name "Net-(U3-RF1)") (class "Default")
      (node (ref "C11") (pin "2") (pinfunction "2_2") (pintype "passive"))
      (node (ref "U3") (pin "1") (pinfunction "RF1_1") (pintype "passive"))
    )
    (net (code "59") (name "Net-(U3-RF2)") (class "Default")
      (node (ref "C20") (pin "1") (pinfunction "1_1") (pintype "passive"))
      (node (ref "C62") (pin "2") (pinfunction "2_2") (pintype "passive"))
      (node (ref "L4") (pin "2") (pinfunction "2_2") (pintype "passive"))
      (node (ref "U3") (pin "3") (pinfunction "RF2_3") (pintype "passive"))
    )
    (net (code "60") (name "Net-(U3-RFC)") (class "Default")
      (node (ref "C17") (pin "1") (pinfunction "1_1") (pintype "passive"))
      (node (ref "U3") (pin "5") (pinfunction "RFC_5") (pintype "passive"))
    )
    (net (code "61") (name "Net-(U4-CTRL)") (class "Default")
      (node (ref "C41") (pin "2") (pinfunction "2_2") (pintype "passive"))
      (node (ref "R14") (pin "2") (pinfunction "2_2") (pintype "passive"))
      (node (ref "U4") (pin "4") (pinfunction "CTRL_4") (pintype "input"))
    )
    (net (code "62") (name "Net-(U4-RF1)") (class "Default")
      (node (ref "C24") (pin "2") (pinfunction "2_2") (pintype "passive"))
      (node (ref "C36") (pin "1") (pinfunction "1_1") (pintype "passive"))
      (node (ref "L8") (pin "2") (pinfunction "2_2") (pintype "passive"))
      (node (ref "U4") (pin "1") (pinfunction "RF1_1") (pintype "passive"))
    )
    (net (code "63") (name "Net-(U4-RF2)") (class "Default")
      (node (ref "C38") (pin "2") (pinfunction "2_2") (pintype "passive"))
      (node (ref "U4") (pin "3") (pinfunction "RF2_3") (pintype "passive"))
    )
    (net (code "64") (name "Net-(U4-RFC)") (class "Default")
      (node (ref "C39") (pin "1") (pinfunction "1_1") (pintype "passive"))
      (node (ref "U4") (pin "5") (pinfunction "RFC_5") (pintype "passive"))
    )
    (net (code "65") (name "unconnected-(RN2-Pad1)") (class "Default")
      (node (ref "RN2") (pin "1") (pinfunction "1_1") (pintype "passive+no_connect"))
    )
    (net (code "66") (name "unconnected-(RN2-Pad8)") (class "Default")
      (node (ref "RN2") (pin "8") (pinfunction "8_8") (pintype "passive+no_connect"))
    )
  )
)
